# Programmer.net
KiCad netlist of a schematic drawn in EAGLE
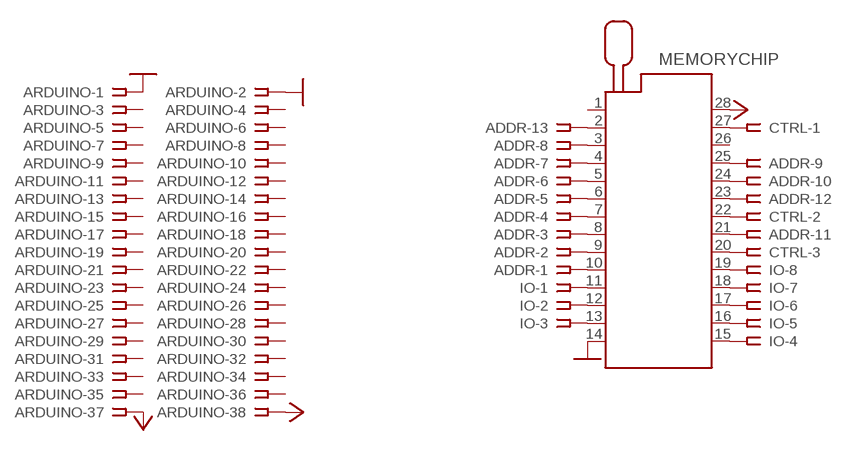
[diagram p0: schematic, sheet 1]

(export (version "E")
  (design (tool "Eeschema 10.0.6"))
  (components
    (comp (ref "ADDR")
      (value "SSW-113-02-G-S-RA")
      (footprint "eagle-import:SSW-113-02-G-S-RA")
      (fields (field (name "MF") "Samtec Inc."))
      (libsource (lib "eagle-import") (part "SSW-113-02-G-S-RA"))
    )
    (comp (ref "ARDUINO")
      (value "SSW-119-02-G-D")
      (footprint "eagle-import:SSW-119-02-G-D")
      (fields (field (name "MF") "Samtec Inc."))
      (libsource (lib "eagle-import") (part "SSW-119-02-G-D"))
    )
    (comp (ref "CTRL")
      (value "SSW-103-02-G-S-RA")
      (footprint "eagle-import:SSW-103-02-G-S-RA")
      (fields (field (name "MF") "Samtec Inc."))
      (libsource (lib "eagle-import") (part "SSW-103-02-G-S-RA"))
    )
    (comp (ref "IO")
      (value "SSW-108-02-G-S-RA")
      (footprint "eagle-import:SSW-108-02-G-S-RA")
      (fields (field (name "MF") "Samtec Inc."))
      (libsource (lib "eagle-import") (part "SSW-108-02-G-S-RA"))
    )
    (comp (ref "MEMORYCHIP")
      (value "228-1277-00-0602J")
      (footprint "eagle-import:228-1277-00-0602J")
      (fields (field (name "MF") "3M"))
      (libsource (lib "eagle-import") (part "228-?00-0602J1277-"))
    )
  )
  (nets
    (net (code "1") (name "GND") (class "Default")
      (node (ref "ARDUINO") (pin "1") (pinfunction "1_1") (pintype "passive"))
      (node (ref "ARDUINO") (pin "2") (pinfunction "1_2") (pintype "passive"))
      (node (ref "MEMORYCHIP") (pin "14") (pinfunction "14_14") (pintype "passive"))
    )
    (net (code "2") (name "Net-(ADDR-Pad1)") (class "Default")
      (node (ref "ADDR") (pin "1") (pinfunction "1_1") (pintype "passive"))
      (node (ref "MEMORYCHIP") (pin "10") (pinfunction "10_10") (pintype "passive"))
    )
    (net (code "3") (name "Net-(ADDRB-1)") (class "Default")
      (node (ref "ADDR") (pin "10") (pinfunction "1_10") (pintype "passive"))
      (node (ref "MEMORYCHIP") (pin "24") (pinfunction "24_24") (pintype "passive"))
    )
    (net (code "4") (name "Net-(ADDRC-1)") (class "Default")
      (node (ref "ADDR") (pin "11") (pinfunction "1_11") (pintype "passive"))
      (node (ref "MEMORYCHIP") (pin "21") (pinfunction "21_21") (pintype "passive"))
    )
    (net (code "5") (name "Net-(ADDRD-1)") (class "Default")
      (node (ref "ADDR") (pin "12") (pinfunction "1_12") (pintype "passive"))
      (node (ref "MEMORYCHIP") (pin "23") (pinfunction "23_23") (pintype "passive"))
    )
    (net (code "6") (name "Net-(ADDRE-1)") (class "Default")
      (node (ref "ADDR") (pin "13") (pinfunction "1_13") (pintype "passive"))
      (node (ref "MEMORYCHIP") (pin "2") (pinfunction "2_2") (pintype "passive"))
    )
    (net (code "7") (name "Net-(ADDRF-1)") (class "Default")
      (node (ref "ADDR") (pin "2") (pinfunction "1_2") (pintype "passive"))
      (node (ref "MEMORYCHIP") (pin "9") (pinfunction "9_9") (pintype "passive"))
    )
    (net (code "8") (name "Net-(ADDRG-1)") (class "Default")
      (node (ref "ADDR") (pin "3") (pinfunction "1_3") (pintype "passive"))
      (node (ref "MEMORYCHIP") (pin "8") (pinfunction "8_8") (pintype "passive"))
    )
    (net (code "9") (name "Net-(ADDRH-1)") (class "Default")
      (node (ref "ADDR") (pin "4") (pinfunction "1_4") (pintype "passive"))
      (node (ref "MEMORYCHIP") (pin "7") (pinfunction "7_7") (pintype "passive"))
    )
    (net (code "10") (name "Net-(ADDRI-1)") (class "Default")
      (node (ref "ADDR") (pin "5") (pinfunction "1_5") (pintype "passive"))
      (node (ref "MEMORYCHIP") (pin "6") (pinfunction "6_6") (pintype "passive"))
    )
    (net (code "11") (name "Net-(ADDRJ-1)") (class "Default")
      (node (ref "ADDR") (pin "6") (pinfunction "1_6") (pintype "passive"))
      (node (ref "MEMORYCHIP") (pin "5") (pinfunction "5_5") (pintype "passive"))
    )
    (net (code "12") (name "Net-(ADDRK-1)") (class "Default")
      (node (ref "ADDR") (pin "7") (pinfunction "1_7") (pintype "passive"))
      (node (ref "MEMORYCHIP") (pin "4") (pinfunction "4_4") (pintype "passive"))
    )
    (net (code "13") (name "Net-(ADDRL-1)") (class "Default")
      (node (ref "ADDR") (pin "8") (pinfunction "1_8") (pintype "passive"))
      (node (ref "MEMORYCHIP") (pin "3") (pinfunction "3_3") (pintype "passive"))
    )
    (net (code "14") (name "Net-(ADDRM-1)") (class "Default")
      (node (ref "ADDR") (pin "9") (pinfunction "1_9") (pintype "passive"))
      (node (ref "MEMORYCHIP") (pin "25") (pinfunction "25_25") (pintype "passive"))
    )
    (net (code "15") (name "Net-(CTRL-Pad1)") (class "Default")
      (node (ref "CTRL") (pin "1") (pinfunction "1_1") (pintype "passive"))
      (node (ref "MEMORYCHIP") (pin "27") (pinfunction "27_27") (pintype "passive"))
    )
    (net (code "16") (name "Net-(CTRLB-1)") (class "Default")
      (node (ref "CTRL") (pin "2") (pinfunction "1_2") (pintype "passive"))
      (node (ref "MEMORYCHIP") (pin "22") (pinfunction "22_22") (pintype "passive"))
    )
    (net (code "17") (name "Net-(CTRLC-1)") (class "Default")
      (node (ref "CTRL") (pin "3") (pinfunction "1_3") (pintype "passive"))
      (node (ref "MEMORYCHIP") (pin "20") (pinfunction "20_20") (pintype "passive"))
    )
    (net (code "18") (name "Net-(IO-Pad1)") (class "Default")
      (node (ref "IO") (pin "1") (pinfunction "1_1") (pintype "passive"))
      (node (ref "MEMORYCHIP") (pin "11") (pinfunction "11_11") (pintype "passive"))
    )
    (net (code "19") (name "Net-(IOB-1)") (class "Default")
      (node (ref "IO") (pin "2") (pinfunction "1_2") (pintype "passive"))
      (node (ref "MEMORYCHIP") (pin "12") (pinfunction "12_12") (pintype "passive"))
    )
    (net (code "20") (name "Net-(IOC-1)") (class "Default")
      (node (ref "IO") (pin "3") (pinfunction "1_3") (pintype "passive"))
      (node (ref "MEMORYCHIP") (pin "13") (pinfunction "13_13") (pintype "passive"))
    )
    (net (code "21") (name "Net-(IOD-1)") (class "Default")
      (node (ref "IO") (pin "4") (pinfunction "1_4") (pintype "passive"))
      (node (ref "MEMORYCHIP") (pin "15") (pinfunction "15_15") (pintype "passive"))
    )
    (net (code "22") (name "Net-(IOE-1)") (class "Default")
      (node (ref "IO") (pin "5") (pinfunction "1_5") (pintype "passive"))
      (node (ref "MEMORYCHIP") (pin "16") (pinfunction "16_16") (pintype "passive"))
    )
    (net (code "23") (name "Net-(IOF-1)") (class "Default")
      (node (ref "IO") (pin "6") (pinfunction "1_6") (pintype "passive"))
      (node (ref "MEMORYCHIP") (pin "17") (pinfunction "17_17") (pintype "passive"))
    )
    (net (code "24") (name "Net-(IOG-1)") (class "Default")
      (node (ref "IO") (pin "7") (pinfunction "1_7") (pintype "passive"))
      (node (ref "MEMORYCHIP") (pin "18") (pinfunction "18_18") (pintype "passive"))
    )
    (net (code "25") (name "Net-(IOH-1)") (class "Default")
      (node (ref "IO") (pin "8") (pinfunction "1_8") (pintype "passive"))
      (node (ref "MEMORYCHIP") (pin "19") (pinfunction "19_19") (pintype "passive"))
    )
    (net (code "26") (name "VCC") (class "Default")
      (node (ref "ARDUINO") (pin "37") (pinfunction "1_37") (pintype "passive"))
      (node (ref "ARDUINO") (pin "38") (pinfunction "1_38") (pintype "passive"))
      (node (ref "MEMORYCHIP") (pin "28") (pinfunction "28_28") (pintype "passive"))
    )
    (net (code "27") (name "unconnected-(ARDUINOAA-1-Pad33)") (class "Default")
      (node (ref "ARDUINO") (pin "33") (pinfunction "1_33") (pintype "passive"))
    )
    (net (code "28") (name "unconnected-(ARDUINOAB-1-Pad34)") (class "Default")
      (node (ref "ARDUINO") (pin "34") (pinfunction "1_34") (pintype "passive"))
    )
    (net (code "29") (name "unconnected-(ARDUINOAC-1-Pad35)") (class "Default")
      (node (ref "ARDUINO") (pin "35") (pinfunction "1_35") (pintype "passive"))
    )
    (net (code "30") (name "unconnected-(ARDUINOAD-1-Pad36)") (class "Default")
      (node (ref "ARDUINO") (pin "36") (pinfunction "1_36") (pintype "passive"))
    )
    (net (code "31") (name "unconnected-(ARDUINOAG-1-Pad4)") (class "Default")
      (node (ref "ARDUINO") (pin "4") (pinfunction "1_4") (pintype "passive"))
    )
    (net (code "32") (name "unconnected-(ARDUINOAH-1-Pad5)") (class "Default")
      (node (ref "ARDUINO") (pin "5") (pinfunction "1_5") (pintype "passive"))
    )
    (net (code "33") (name "unconnected-(ARDUINOAI-1-Pad6)") (class "Default")
      (node (ref "ARDUINO") (pin "6") (pinfunction "1_6") (pintype "passive"))
    )
    (net (code "34") (name "unconnected-(ARDUINOAJ-1-Pad7)") (class "Default")
      (node (ref "ARDUINO") (pin "7") (pinfunction "1_7") (pintype "passive"))
    )
    (net (code "35") (name "unconnected-(ARDUINOAK-1-Pad8)") (class "Default")
      (node (ref "ARDUINO") (pin "8") (pinfunction "1_8") (pintype "passive"))
    )
    (net (code "36") (name "unconnected-(ARDUINOAL-1-Pad9)") (class "Default")
      (node (ref "ARDUINO") (pin "9") (pinfunction "1_9") (pintype "passive"))
    )
    (net (code "37") (name "unconnected-(ARDUINOB-1-Pad10)") (class "Default")
      (node (ref "ARDUINO") (pin "10") (pinfunction "1_10") (pintype "passive"))
    )
    (net (code "38") (name "unconnected-(ARDUINOC-1-Pad11)") (class "Default")
      (node (ref "ARDUINO") (pin "11") (pinfunction "1_11") (pintype "passive"))
    )
    (net (code "39") (name "unconnected-(ARDUINOD-1-Pad12)") (class "Default")
      (node (ref "ARDUINO") (pin "12") (pinfunction "1_12") (pintype "passive"))
    )
    (net (code "40") (name "unconnected-(ARDUINOE-1-Pad13)") (class "Default")
      (node (ref "ARDUINO") (pin "13") (pinfunction "1_13") (pintype "passive"))
    )
    (net (code "41") (name "unconnected-(ARDUINOF-1-Pad14)") (class "Default")
      (node (ref "ARDUINO") (pin "14") (pinfunction "1_14") (pintype "passive"))
    )
    (net (code "42") (name "unconnected-(ARDUINOG-1-Pad15)") (class "Default")
      (node (ref "ARDUINO") (pin "15") (pinfunction "1_15") (pintype "passive"))
    )
    (net (code "43") (name "unconnected-(ARDUINOH-1-Pad16)") (class "Default")
      (node (ref "ARDUINO") (pin "16") (pinfunction "1_16") (pintype "passive"))
    )
    (net (code "44") (name "unconnected-(ARDUINOI-1-Pad17)") (class "Default")
      (node (ref "ARDUINO") (pin "17") (pinfunction "1_17") (pintype "passive"))
    )
    (net (code "45") (name "unconnected-(ARDUINOJ-1-Pad18)") (class "Default")
      (node (ref "ARDUINO") (pin "18") (pinfunction "1_18") (pintype "passive"))
    )
    (net (code "46") (name "unconnected-(ARDUINOK-1-Pad19)") (class "Default")
      (node (ref "ARDUINO") (pin "19") (pinfunction "1_19") (pintype "passive"))
    )
    (net (code "47") (name "unconnected-(ARDUINOM-1-Pad20)") (class "Default")
      (node (ref "ARDUINO") (pin "20") (pinfunction "1_20") (pintype "passive"))
    )
    (net (code "48") (name "unconnected-(ARDUINON-1-Pad21)") (class "Default")
      (node (ref "ARDUINO") (pin "21") (pinfunction "1_21") (pintype "passive"))
    )
    (net (code "49") (name "unconnected-(ARDUINOO-1-Pad22)") (class "Default")
      (node (ref "ARDUINO") (pin "22") (pinfunction "1_22") (pintype "passive"))
    )
    (net (code "50") (name "unconnected-(ARDUINOP-1-Pad23)") (class "Default")
      (node (ref "ARDUINO") (pin "23") (pinfunction "1_23") (pintype "passive"))
    )
    (net (code "51") (name "unconnected-(ARDUINOQ-1-Pad24)") (class "Default")
      (node (ref "ARDUINO") (pin "24") (pinfunction "1_24") (pintype "passive"))
    )
    (net (code "52") (name "unconnected-(ARDUINOR-1-Pad25)") (class "Default")
      (node (ref "ARDUINO") (pin "25") (pinfunction "1_25") (pintype "passive"))
    )
    (net (code "53") (name "unconnected-(ARDUINOS-1-Pad26)") (class "Default")
      (node (ref "ARDUINO") (pin "26") (pinfunction "1_26") (pintype "passive"))
    )
    (net (code "54") (name "unconnected-(ARDUINOT-1-Pad27)") (class "Default")
      (node (ref "ARDUINO") (pin "27") (pinfunction "1_27") (pintype "passive"))
    )
    (net (code "55") (name "unconnected-(ARDUINOU-1-Pad28)") (class "Default")
      (node (ref "ARDUINO") (pin "28") (pinfunction "1_28") (pintype "passive"))
    )
    (net (code "56") (name "unconnected-(ARDUINOV-1-Pad29)") (class "Default")
      (node (ref "ARDUINO") (pin "29") (pinfunction "1_29") (pintype "passive"))
    )
    (net (code "57") (name "unconnected-(ARDUINOW-1-Pad3)") (class "Default")
      (node (ref "ARDUINO") (pin "3") (pinfunction "1_3") (pintype "passive"))
    )
    (net (code "58") (name "unconnected-(ARDUINOX-1-Pad30)") (class "Default")
      (node (ref "ARDUINO") (pin "30") (pinfunction "1_30") (pintype "passive"))
    )
    (net (code "59") (name "unconnected-(ARDUINOY-1-Pad31)") (class "Default")
      (node (ref "ARDUINO") (pin "31") (pinfunction "1_31") (pintype "passive"))
    )
    (net (code "60") (name "unconnected-(ARDUINOZ-1-Pad32)") (class "Default")
      (node (ref "ARDUINO") (pin "32") (pinfunction "1_32") (pintype "passive"))
    )
    (net (code "61") (name "unconnected-(MEMORYCHIP-Pad1)") (class "Default")
      (node (ref "MEMORYCHIP") (pin "1") (pinfunction "1_1") (pintype "passive"))
    )
    (net (code "62") (name "unconnected-(MEMORYCHIP-Pad26)") (class "Default")
      (node (ref "MEMORYCHIP") (pin "26") (pinfunction "26_26") (pintype "passive"))
    )
  )
)
